# STSPIN32F0A-bldc-driver.net
KiCad netlist of a schematic drawn in Altium Designer
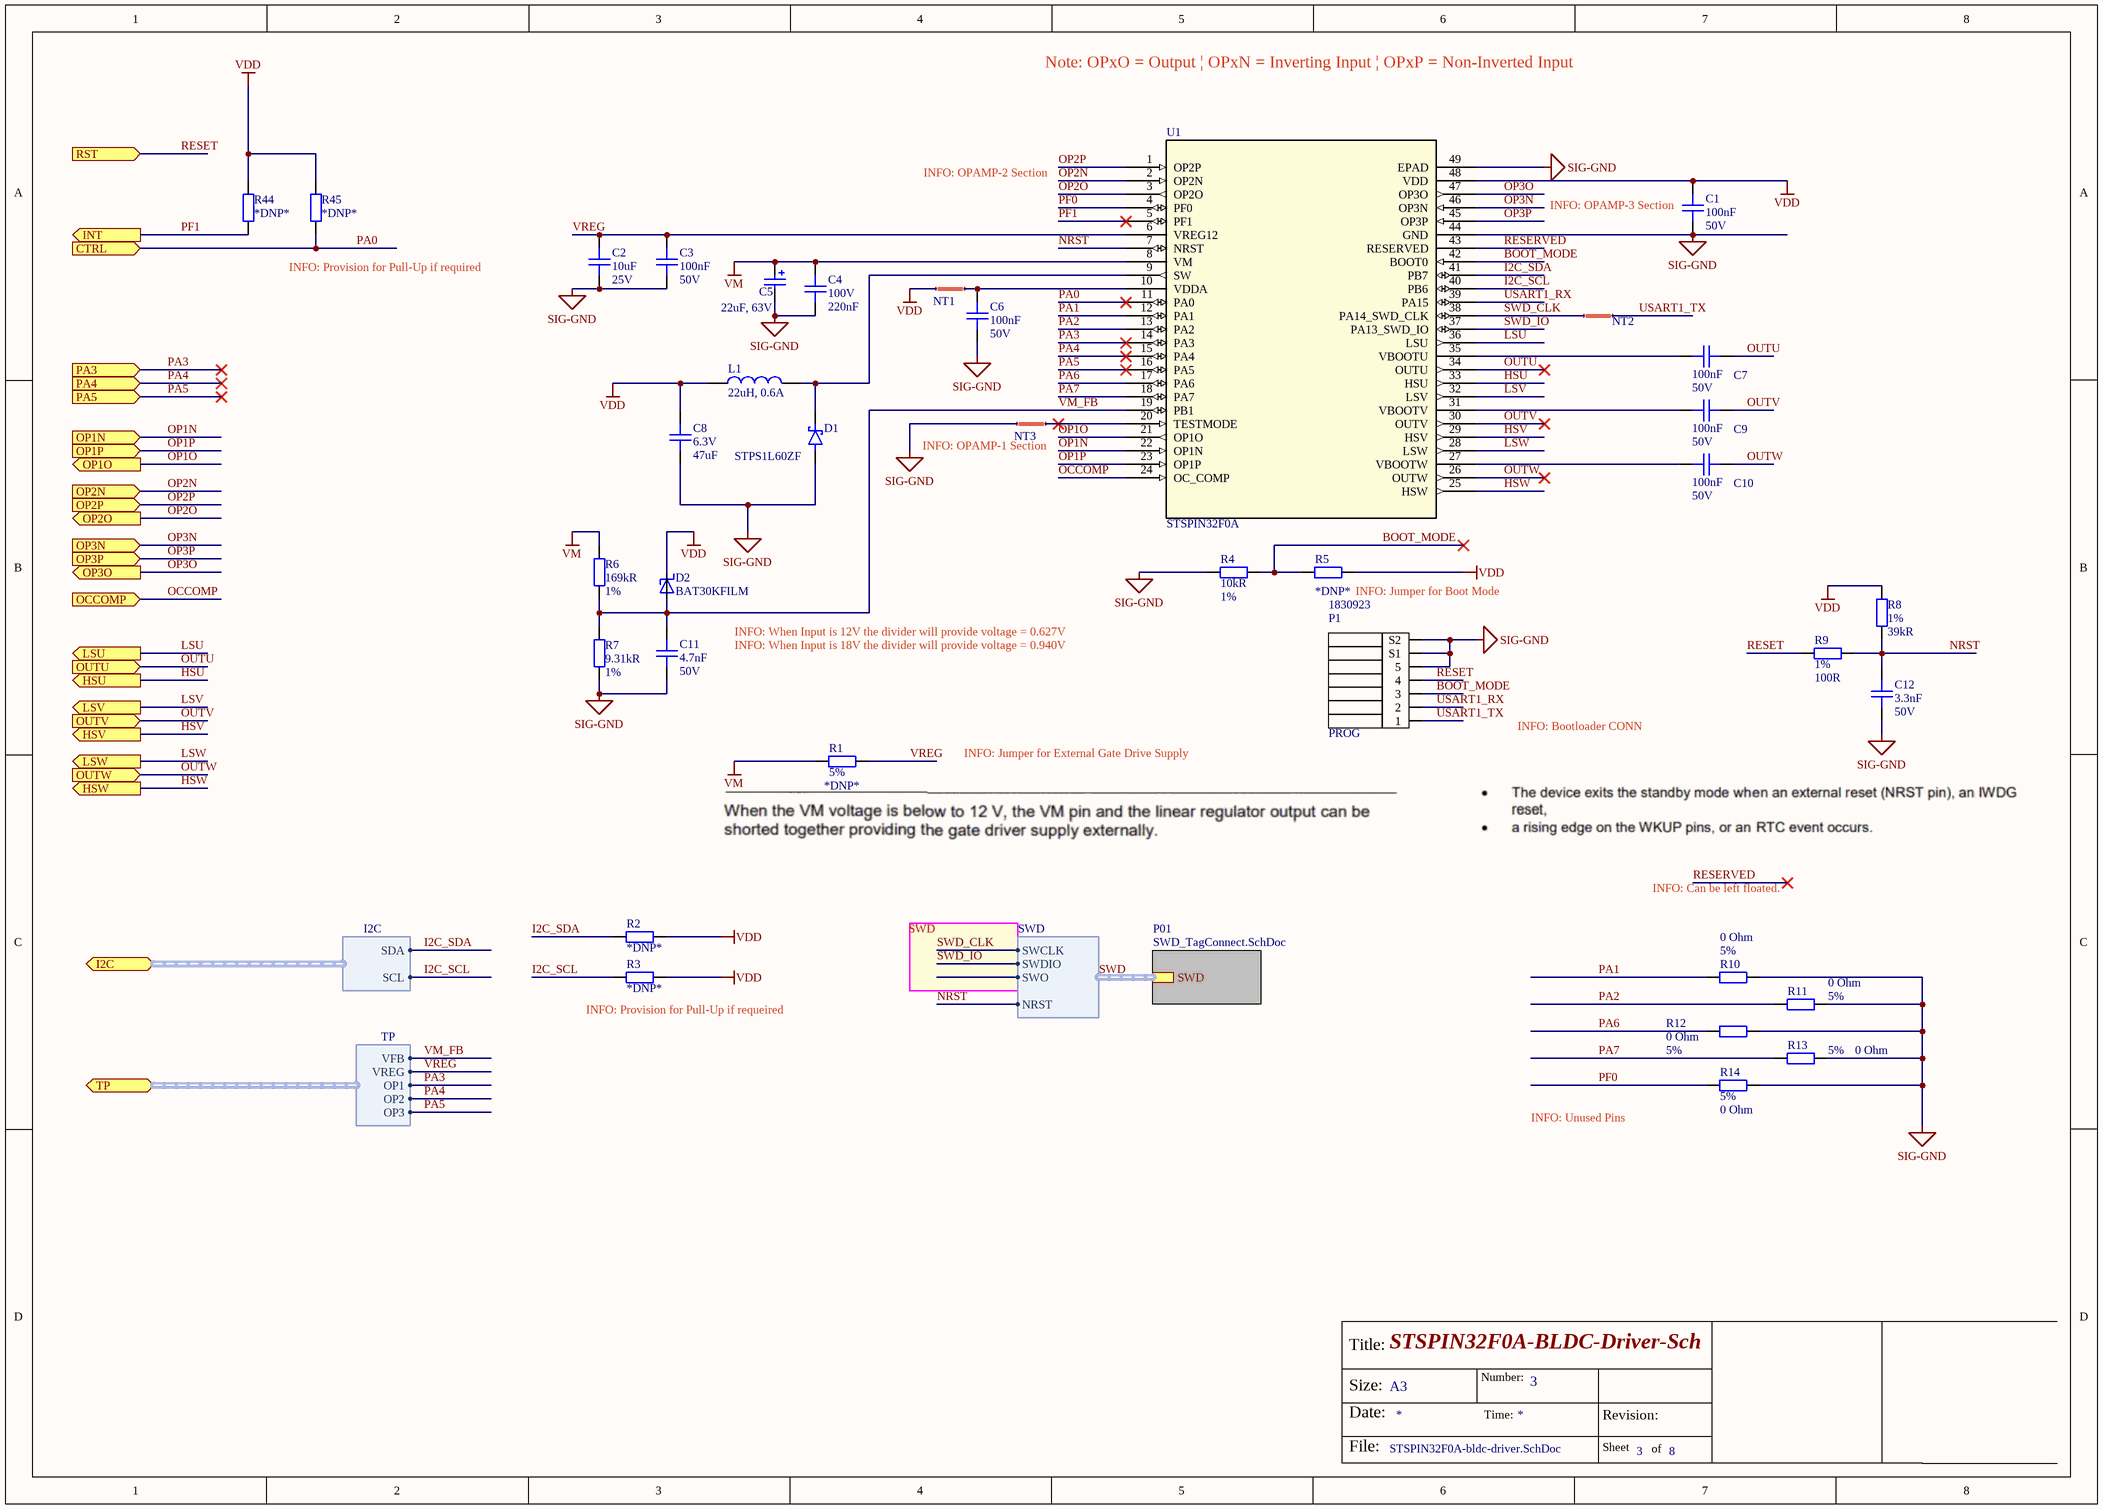
[diagram p0: STSPIN32F0A-bldc-driver.SchDoc]

(export (version "E")
  (design (tool "Eeschema 10.0.6"))
  (components
    (comp (ref "C1")
      (value "CAP CER 0.1UF 50V X7R 0402")
      (footprint "C0402")
      (description "0.1µF ±10% 50V Ceramic Capacitor X7R 0402 (1005 Metric)")
      (fields
        (field (name "MANUFACTURER") "TDK")
        (field (name "MANUFACTURER PART NUMBER") "CGA2B3X7R1H104K050BB")
        (field (name "CAPACITANCE") "100nF")
        (field (name "VOLTAGE") "50V")
      )
      (libsource (lib "Control_Board_Model_C201") (part "CAP CER 0.1UF 50V X7R 0402"))
    )
    (comp (ref "C2")
      (value "CAP CER 10UF 25V X7R 1206")
      (footprint "C1206")
      (description "10µF ±10% 25V Ceramic Capacitor X7R 1206 (3216 Metric)")
      (fields
        (field (name "MANUFACTURER") "Yageo")
        (field (name "MANUFACTURER PART NUMBER") "CC1206KKX7R8BB106")
        (field (name "CAPACITANCE") "10uF")
        (field (name "VOLTAGE RATING") "25V")
      )
      (libsource (lib "Control_Board_Model_C201") (part "CAP CER 10UF 25V X7R 1206"))
    )
    (comp (ref "C3")
      (value "CAP CER 0.1UF 50V X7R 0402")
      (footprint "C0402")
      (description "0.1µF ±10% 50V Ceramic Capacitor X7R 0402 (1005 Metric)")
      (fields
        (field (name "MANUFACTURER") "TDK")
        (field (name "MANUFACTURER PART NUMBER") "CGA2B3X7R1H104K050BB")
        (field (name "CAPACITANCE") "100nF")
        (field (name "VOLTAGE") "50V")
      )
      (libsource (lib "Control_Board_Model_C201") (part "CAP CER 0.1UF 50V X7R 0402"))
    )
    (comp (ref "C4")
      (value "CAP CER 220nF 100V X7R 0805")
      (footprint "C0805")
      (description "220nF ±10% 100V Ceramic Capacitor X7R 0805 (2012 Metric)")
      (fields
        (field (name "MANUFACTURER") "KEMET")
        (field (name "MANUFACTURER PART NUMBER") "C0805C224K1RECAUTO")
        (field (name "VOLTAGE RATING") "100V")
        (field (name "CAPACITANCE") "220nF")
      )
      (libsource (lib "Control_Board_Model_C201") (part "CAP CER 22UF 10V X5R 0805"))
    )
    (comp (ref "C5")
      (value "22uF, 63V")
      (footprint "WCAP-ASLL_D6.3H7.7")
      (description "WCAP-ASLL Aluminum Electrolytic Capacitor, V-Chip, SMT, D6.3xH7.7mm, 22uF, 63V")
      (fields
        (field (name "MANUFACTURER PART NUMBER") "865060745003")
        (field (name "MANUFACTURER") "Wurth Elektronik")
      )
      (libsource (lib "Altium_WCAP-ASLL (rev20b)") (part "865060745003"))
    )
    (comp (ref "C6")
      (value "CAP CER 0.1UF 50V X7R 0402")
      (footprint "C0402")
      (description "0.1µF ±10% 50V Ceramic Capacitor X7R 0402 (1005 Metric)")
      (fields
        (field (name "MANUFACTURER") "TDK")
        (field (name "MANUFACTURER PART NUMBER") "CGA2B3X7R1H104K050BB")
        (field (name "CAPACITANCE") "100nF")
        (field (name "VOLTAGE") "50V")
      )
      (libsource (lib "Control_Board_Model_C201") (part "CAP CER 0.1UF 50V X7R 0402"))
    )
    (comp (ref "C7")
      (value "CAP CER 0.1UF 50V X7R 0402")
      (footprint "C0402")
      (description "0.1µF ±10% 50V Ceramic Capacitor X7R 0402 (1005 Metric)")
      (fields
        (field (name "MANUFACTURER") "TDK")
        (field (name "MANUFACTURER PART NUMBER") "CGA2B3X7R1H104K050BB")
        (field (name "CAPACITANCE") "100nF")
        (field (name "VOLTAGE") "50V")
      )
      (libsource (lib "Control_Board_Model_C201") (part "CAP CER 0.1UF 50V X7R 0402"))
    )
    (comp (ref "C8")
      (value "CAP CER 47UF 6.3V X5R 0603")
      (footprint "C0603")
      (description "47µF ±20% 6.3V Ceramic Capacitor X5R 0603 (1608 Metric)")
      (fields
        (field (name "MANUFACTURER") "AVX Corporation")
        (field (name "MANUFACTURER PART NUMBER") "06036D476MAT2A")
        (field (name "VOLTAGE RATING") "6.3V")
        (field (name "CAPACITANCE") "47uF")
      )
      (libsource (lib "Control_Board_Model_C201") (part "CAP CER 4.7UF 16V X5R 0603"))
    )
    (comp (ref "C9")
      (value "CAP CER 0.1UF 50V X7R 0402")
      (footprint "C0402")
      (description "0.1µF ±10% 50V Ceramic Capacitor X7R 0402 (1005 Metric)")
      (fields
        (field (name "MANUFACTURER") "TDK")
        (field (name "MANUFACTURER PART NUMBER") "CGA2B3X7R1H104K050BB")
        (field (name "CAPACITANCE") "100nF")
        (field (name "VOLTAGE") "50V")
      )
      (libsource (lib "Control_Board_Model_C201") (part "CAP CER 0.1UF 50V X7R 0402"))
    )
    (comp (ref "C10")
      (value "CAP CER 0.1UF 50V X7R 0402")
      (footprint "C0402")
      (description "0.1µF ±10% 50V Ceramic Capacitor X7R 0402 (1005 Metric)")
      (fields
        (field (name "MANUFACTURER") "TDK")
        (field (name "MANUFACTURER PART NUMBER") "CGA2B3X7R1H104K050BB")
        (field (name "CAPACITANCE") "100nF")
        (field (name "VOLTAGE") "50V")
      )
      (libsource (lib "Control_Board_Model_C201") (part "CAP CER 0.1UF 50V X7R 0402"))
    )
    (comp (ref "C11")
      (value "CAP CER 4.7nF 50V X7R 0402")
      (footprint "C0402")
      (description "4.7nF ±10% 50V Ceramic Capacitor X7R 0402 (1005 Metric)")
      (fields
        (field (name "MANUFACTURER") "KEMET")
        (field (name "MANUFACTURER PART NUMBER") "C0402C472K5RECAUTO")
        (field (name "CAPACITANCE") "4.7nF")
        (field (name "VOLTAGE RATING") "50V")
      )
      (libsource (lib "Control_Board_Model_C201") (part "CAP CER 0.047UF 50V X7R 0402"))
    )
    (comp (ref "C12")
      (value "CAP CER 0.1UF 50V X7R 0402")
      (footprint "C0402")
      (description "0.1µF ±10% 50V Ceramic Capacitor X7R 0402 (1005 Metric)")
      (fields
        (field (name "MANUFACTURER") "KEMET")
        (field (name "MANUFACTURER PART NUMBER") "C0402C332K5RECAUTO")
        (field (name "CAPACITANCE") "3.3nF")
        (field (name "VOLTAGE") "50V")
      )
      (libsource (lib "Control_Board_Model_C201") (part "CAP CER 0.1UF 50V X7R 0402"))
    )
    (comp (ref "D1")
      (value "STPS1L60ZF")
      (footprint "DIO_STPS1L60ZF")
      (description "Diode Schottky 60V 1A Surface Mount SOD-123F")
      (fields
        (field (name "MANUFACTURER") "STMicroelectronics")
        (field (name "MANUFACTURER PART NUMBER") "STPS1L60ZF")
      )
      (libsource (lib "STPS1L60ZF") (part "STPS1L60ZF"))
    )
    (comp (ref "D2")
      (value "BAT30KFILM")
      (footprint "SOD523")
      (description "Schottky Diode 30V 300mA (DC) Surface Mount SOD-523")
      (fields (field (name "MANUFACTURER") "STMicroelectronics"))
      (libsource (lib "BAT30KFILM") (part "BAT30KFILM"))
    )
    (comp (ref "L1")
      (value "22uH, 0.6A")
      (footprint "WE-LQS_3015")
      (description "WE-LQS SMT Power Inductor, size 3015, 22uH, 0.6A")
      (fields
        (field (name "MANUFACTURER") "Wurth Elektronik")
        (field (name "MANUFACTURER PART NUMBER") "74404032220")
      )
      (libsource (lib "WE-LQS (rev20b)") (part "74404032220"))
    )
    (comp (ref "NT1")
      (value "Net Tie")
      (footprint "Net Tie 6x30mil")
      (libsource (lib "Control_Board_Model_C201") (part "Net Tie Line"))
    )
    (comp (ref "NT2")
      (value "Net Tie")
      (footprint "Net Tie 6x30mil")
      (libsource (lib "Control_Board_Model_C201") (part "Net Tie Line"))
    )
    (comp (ref "NT3")
      (value "Net Tie")
      (footprint "Net Tie 6x30mil")
      (libsource (lib "Control_Board_Model_C201") (part "Net Tie Line"))
    )
    (comp (ref "P1")
      (value "PROG")
      (footprint "JST_S5B-ZR-SM4A-TF(LF)(SN)")
      (description "Connector Header SMD, Right Angle 4 position 0.059\" (1.50mm)")
      (fields
        (field (name "MANUFACTURER") "JST")
        (field (name "MANUFACTURER PART NUMBER") "S4B-ZR-SM4A-TF")
        (field (name "SUPPLIER PART NUMBER 1") "1830923")
      )
      (libsource (lib "JST-ZR-v1.3") (part "JST_S5B-ZR-SM4A-TF(LF)(SN)"))
    )
    (comp (ref "R1")
      (value "*DNP*")
      (footprint "R0402")
      (description "0 Ohms Jumper 0.063W, 1/16W Chip Resistor 0402 (1005 Metric) Moisture Resistant Thick Film")
      (fields
        (field (name "MANUFACTURER") "Yageo")
        (field (name "MANUFACTURER PART NUMBER") "RC0402JR-070RL")
        (field (name "TOLERANCE") "5%")
      )
      (libsource (lib "Control_Board_Model_C201") (part "RES SMD 0 OHM JUMPER 1/16W 0402"))
    )
    (comp (ref "R2")
      (value "RES SMD 4.75K OHM 1% 1/16W 0402")
      (footprint "R0402")
      (description "4.75 kOhms ±1% 0.063W, 1/16W Chip Resistor 0402 (1005 Metric) Moisture Resistant Thick Film")
      (fields
        (field (name "MANUFACTURER") "Yageo")
        (field (name "MANUFACTURER PART NUMBER") "RC0402FR-074K75P")
        (field (name "RESISTANCE") "*DNP*")
      )
      (libsource (lib "Control_Board_Model_C201") (part "RES SMD 4.75K OHM 1% 1/16W 0402"))
    )
    (comp (ref "R3")
      (value "RES SMD 4.75K OHM 1% 1/16W 0402")
      (footprint "R0402")
      (description "4.75 kOhms ±1% 0.063W, 1/16W Chip Resistor 0402 (1005 Metric) Moisture Resistant Thick Film")
      (fields
        (field (name "MANUFACTURER") "Yageo")
        (field (name "MANUFACTURER PART NUMBER") "RC0402FR-074K75P")
        (field (name "RESISTANCE") "*DNP*")
      )
      (libsource (lib "Control_Board_Model_C201") (part "RES SMD 4.75K OHM 1% 1/16W 0402"))
    )
    (comp (ref "R4")
      (value "RES SMD 10K OHM 1% 1/16W 0402")
      (footprint "R0402")
      (description "10 kOhms ±1% 0.063W, 1/16W Chip Resistor 0402 (1005 Metric) Moisture Resistant Thick Film")
      (fields
        (field (name "MANUFACTURER") "Yageo")
        (field (name "MANUFACTURER PART NUMBER") "RC0402FR-0710KP")
        (field (name "RESISTANCE") "10kR")
        (field (name "TOLERANCE") "1%")
      )
      (libsource (lib "Control_Board_Model_C201") (part "RES SMD 10K OHM 1% 1/16W 0402"))
    )
    (comp (ref "R5")
      (value "*DNP*")
      (footprint "R0402")
      (description "0 Ohms Jumper 0.063W, 1/16W Chip Resistor 0402 (1005 Metric) Moisture Resistant Thick Film")
      (fields
        (field (name "MANUFACTURER") "Yageo")
        (field (name "MANUFACTURER PART NUMBER") "RC0402JR-070RL")
      )
      (libsource (lib "Control_Board_Model_C201") (part "RES SMD 0 OHM JUMPER 1/16W 0402"))
    )
    (comp (ref "R6")
      (value "RES SMD 169 KOHM 1% 1/8W 0603")
      (footprint "R0603")
      (description "169 kOhms ±1% 0.125W, 1/8W Chip Resistor 0603 (1608 Metric) Automotive AEC-Q200 Thick Film")
      (fields
        (field (name "MANUFACTURER PART NUMBER") "TNPW0603169KBEEA")
        (field (name "MANUFACTURER") "Vishay Dale")
        (field (name "RESISTANCE") "169kR")
        (field (name "TOLERANCE") "1%")
      )
      (libsource (lib "Control_Board_Model_C201") (part "RES SMD 2.26 OHM 1% 1/10W 0603"))
    )
    (comp (ref "R7")
      (value "RES SMD 9.31 KOHM 1% 1/8W 0603")
      (footprint "R0603")
      (description "9.31 kOhms ±1% 0.125W, 1/8W Chip Resistor 0603 (1608 Metric) Automotive AEC-Q200 Thick Film")
      (fields
        (field (name "MANUFACTURER PART NUMBER") "TNPW06039K31BEEA")
        (field (name "MANUFACTURER") "Vishay Dale")
        (field (name "RESISTANCE") "9.31kR")
        (field (name "TOLERANCE") "1%")
      )
      (libsource (lib "Control_Board_Model_C201") (part "RES SMD 2.26 OHM 1% 1/10W 0603"))
    )
    (comp (ref "R8")
      (value "RES SMD 39K OHM 1% 1/10W 0402")
      (footprint "R0402")
      (description "39 kOhms ±1% 0.100W, 1/10W Chip Resistor 0402 (1005 Metric) Moisture Resistant Thick Film")
      (fields
        (field (name "MANUFACTURER") "Panasonic Electronic Components")
        (field (name "MANUFACTURER PART NUMBER") "ERJ-2RKF3902X")
        (field (name "TOLERANCE") "1%")
        (field (name "RESISTANCE") "39kR")
      )
      (libsource (lib "Control_Board_Model_C201") (part "RES SMD 54.9K OHM 1% 1/16W 0402"))
    )
    (comp (ref "R9")
      (value "RES SMD 100 OHM 1% 1/16W 0402")
      (footprint "R0402")
      (description "100 Ohms ±1% 0.063W, 1/16W Chip Resistor 0402 (1005 Metric) Moisture Resistant Thick Film")
      (fields
        (field (name "MANUFACTURER") "Yageo")
        (field (name "MANUFACTURER PART NUMBER") "RC0402FR-07100RL")
        (field (name "TOLERANCE") "1%")
        (field (name "RESISTANCE") "100R")
      )
      (libsource (lib "Control_Board_Model_C201") (part "RES SMD 100 OHM 1% 1/16W 0402"))
    )
    (comp (ref "R10")
      (value "RES SMD 0 OHM JUMPER 1/16W 0402")
      (footprint "R0402")
      (description "0 Ohms Jumper 0.063W, 1/16W Chip Resistor 0402 (1005 Metric) Moisture Resistant Thick Film")
      (fields
        (field (name "MANUFACTURER") "Yageo")
        (field (name "MANUFACTURER PART NUMBER") "RC0402JR-070RL")
        (field (name "TOLERANCE") "5%")
        (field (name "RESISTANCE") "0 Ohm")
      )
      (libsource (lib "Control_Board_Model_C201") (part "RES SMD 0 OHM JUMPER 1/16W 0402"))
    )
    (comp (ref "R11")
      (value "RES SMD 0 OHM JUMPER 1/16W 0402")
      (footprint "R0402")
      (description "0 Ohms Jumper 0.063W, 1/16W Chip Resistor 0402 (1005 Metric) Moisture Resistant Thick Film")
      (fields
        (field (name "MANUFACTURER") "Yageo")
        (field (name "MANUFACTURER PART NUMBER") "RC0402JR-070RL")
        (field (name "TOLERANCE") "5%")
        (field (name "RESISTANCE") "0 Ohm")
      )
      (libsource (lib "Control_Board_Model_C201") (part "RES SMD 0 OHM JUMPER 1/16W 0402"))
    )
    (comp (ref "R12")
      (value "RES SMD 0 OHM JUMPER 1/16W 0402")
      (footprint "R0402")
      (description "0 Ohms Jumper 0.063W, 1/16W Chip Resistor 0402 (1005 Metric) Moisture Resistant Thick Film")
      (fields
        (field (name "MANUFACTURER") "Yageo")
        (field (name "MANUFACTURER PART NUMBER") "RC0402JR-070RL")
        (field (name "TOLERANCE") "5%")
        (field (name "RESISTANCE") "0 Ohm")
      )
      (libsource (lib "Control_Board_Model_C201") (part "RES SMD 0 OHM JUMPER 1/16W 0402"))
    )
    (comp (ref "R13")
      (value "RES SMD 0 OHM JUMPER 1/16W 0402")
      (footprint "R0402")
      (description "0 Ohms Jumper 0.063W, 1/16W Chip Resistor 0402 (1005 Metric) Moisture Resistant Thick Film")
      (fields
        (field (name "MANUFACTURER") "Yageo")
        (field (name "MANUFACTURER PART NUMBER") "RC0402JR-070RL")
        (field (name "TOLERANCE") "5%")
        (field (name "RESISTANCE") "0 Ohm")
      )
      (libsource (lib "Control_Board_Model_C201") (part "RES SMD 0 OHM JUMPER 1/16W 0402"))
    )
    (comp (ref "R14")
      (value "RES SMD 0 OHM JUMPER 1/16W 0402")
      (footprint "R0402")
      (description "0 Ohms Jumper 0.063W, 1/16W Chip Resistor 0402 (1005 Metric) Moisture Resistant Thick Film")
      (fields
        (field (name "MANUFACTURER") "Yageo")
        (field (name "MANUFACTURER PART NUMBER") "RC0402JR-070RL")
        (field (name "TOLERANCE") "5%")
        (field (name "RESISTANCE") "0 Ohm")
      )
      (libsource (lib "Control_Board_Model_C201") (part "RES SMD 0 OHM JUMPER 1/16W 0402"))
    )
    (comp (ref "R44")
      (value "*DNP*")
      (footprint "R0402")
      (description "0 Ohms Jumper 0.063W, 1/16W Chip Resistor 0402 (1005 Metric) Moisture Resistant Thick Film")
      (fields
        (field (name "MANUFACTURER") "Yageo")
        (field (name "MANUFACTURER PART NUMBER") "RC0402JR-070RL")
      )
      (libsource (lib "") (part "RES SMD 0 OHM JUMPER 1/16W 0402_1"))
    )
    (comp (ref "R45")
      (value "*DNP*")
      (footprint "R0402")
      (description "0 Ohms Jumper 0.063W, 1/16W Chip Resistor 0402 (1005 Metric) Moisture Resistant Thick Film")
      (fields
        (field (name "MANUFACTURER") "Yageo")
        (field (name "MANUFACTURER PART NUMBER") "RC0402JR-070RL")
      )
      (libsource (lib "") (part "RES SMD 0 OHM JUMPER 1/16W 0402_1"))
    )
    (comp (ref "U1")
      (value "STSPIN32F0A")
      (footprint "VFQFPN-48_7x7x1mm_STM")
      (description "No Description Available")
      (fields
        (field (name "MANUFACTURER") "STMicroelectronics")
        (field (name "COPYRIGHT") "Copyright (C) 2018 Accelerated Designs. All rights reserved")
      )
      (libsource (lib "STSPIN32F0A") (part "STSPIN32F0A"))
    )
  )
  (nets
    (net (code "4") (name "/BOOT_MODE") (class "Default")
      (node (ref "P1") (pin "3") (pinfunction "3_3") (pintype "passive"))
      (node (ref "R4") (pin "1") (pinfunction "1_1") (pintype "passive"))
      (node (ref "R5") (pin "1") (pinfunction "1_1") (pintype "passive"))
      (node (ref "U1") (pin "42") (pinfunction "BOOT0_42") (pintype "input"))
    )
    (net (code "5") (name "/HSU") (class "Default")
      (node (ref "U1") (pin "33") (pinfunction "HSU_33") (pintype "output"))
    )
    (net (code "6") (name "/HSV") (class "Default")
      (node (ref "U1") (pin "29") (pinfunction "HSV_29") (pintype "output"))
    )
    (net (code "7") (name "/HSW") (class "Default")
      (node (ref "U1") (pin "25") (pinfunction "HSW_25") (pintype "output"))
    )
    (net (code "8") (name "/I2C_SCL") (class "Default")
      (node (ref "R3") (pin "1") (pinfunction "1_1") (pintype "passive"))
      (node (ref "U1") (pin "40") (pinfunction "PB6_40") (pintype "bidirectional"))
    )
    (net (code "9") (name "/I2C_SDA") (class "Default")
      (node (ref "R2") (pin "1") (pinfunction "1_1") (pintype "passive"))
      (node (ref "U1") (pin "41") (pinfunction "PB7_41") (pintype "bidirectional"))
    )
    (net (code "10") (name "/LSU") (class "Default")
      (node (ref "U1") (pin "36") (pinfunction "LSU_36") (pintype "output"))
    )
    (net (code "11") (name "/LSV") (class "Default")
      (node (ref "U1") (pin "32") (pinfunction "LSV_32") (pintype "output"))
    )
    (net (code "12") (name "/LSW") (class "Default")
      (node (ref "U1") (pin "28") (pinfunction "LSW_28") (pintype "output"))
    )
    (net (code "13") (name "/NRST") (class "Default")
      (node (ref "C12") (pin "2") (pinfunction "2_2") (pintype "passive"))
      (node (ref "R8") (pin "1") (pinfunction "1_1") (pintype "passive"))
      (node (ref "R9") (pin "1") (pinfunction "1_1") (pintype "passive"))
      (node (ref "U1") (pin "7") (pinfunction "NRST_7") (pintype "bidirectional"))
    )
    (net (code "14") (name "/OCCOMP") (class "Default")
      (node (ref "U1") (pin "24") (pinfunction "OC_COMP_24") (pintype "input"))
    )
    (net (code "15") (name "/OP1N") (class "Default")
      (node (ref "U1") (pin "22") (pinfunction "OP1N_22") (pintype "input"))
    )
    (net (code "16") (name "/OP1O") (class "Default")
      (node (ref "U1") (pin "21") (pinfunction "OP1O_21") (pintype "output"))
    )
    (net (code "17") (name "/OP1P") (class "Default")
      (node (ref "U1") (pin "23") (pinfunction "OP1P_23") (pintype "input"))
    )
    (net (code "18") (name "/OP2N") (class "Default")
      (node (ref "U1") (pin "2") (pinfunction "OP2N_2") (pintype "input"))
    )
    (net (code "19") (name "/OP2O") (class "Default")
      (node (ref "U1") (pin "3") (pinfunction "OP2O_3") (pintype "output"))
    )
    (net (code "20") (name "/OP2P") (class "Default")
      (node (ref "U1") (pin "1") (pinfunction "OP2P_1") (pintype "input"))
    )
    (net (code "21") (name "/OP3N") (class "Default")
      (node (ref "U1") (pin "46") (pinfunction "OP3N_46") (pintype "input"))
    )
    (net (code "22") (name "/OP3O") (class "Default")
      (node (ref "U1") (pin "47") (pinfunction "OP3O_47") (pintype "output"))
    )
    (net (code "23") (name "/OP3P") (class "Default")
      (node (ref "U1") (pin "45") (pinfunction "OP3P_45") (pintype "input"))
    )
    (net (code "24") (name "/OUTU") (class "Default")
      (node (ref "C7") (pin "2") (pinfunction "2_2") (pintype "passive"))
      (node (ref "U1") (pin "34") (pinfunction "OUTU_34") (pintype "output"))
    )
    (net (code "25") (name "/OUTV") (class "Default")
      (node (ref "C9") (pin "1") (pinfunction "1_1") (pintype "passive"))
      (node (ref "U1") (pin "30") (pinfunction "OUTV_30") (pintype "output"))
    )
    (net (code "26") (name "/OUTW") (class "Default")
      (node (ref "C10") (pin "1") (pinfunction "1_1") (pintype "passive"))
      (node (ref "U1") (pin "26") (pinfunction "OUTW_26") (pintype "output"))
    )
    (net (code "27") (name "/PA0") (class "Default")
      (node (ref "R45") (pin "1") (pinfunction "1_1") (pintype "passive"))
      (node (ref "U1") (pin "11") (pinfunction "PA0_11") (pintype "bidirectional"))
    )
    (net (code "28") (name "/PA1") (class "Default")
      (node (ref "R10") (pin "1") (pinfunction "1_1") (pintype "passive"))
      (node (ref "U1") (pin "12") (pinfunction "PA1_12") (pintype "bidirectional"))
    )
    (net (code "29") (name "/PA2") (class "Default")
      (node (ref "R11") (pin "1") (pinfunction "1_1") (pintype "passive"))
      (node (ref "U1") (pin "13") (pinfunction "PA2_13") (pintype "bidirectional"))
    )
    (net (code "30") (name "/PA3") (class "Default")
      (node (ref "U1") (pin "14") (pinfunction "PA3_14") (pintype "bidirectional+no_connect"))
    )
    (net (code "31") (name "/PA4") (class "Default")
      (node (ref "U1") (pin "15") (pinfunction "PA4_15") (pintype "bidirectional+no_connect"))
    )
    (net (code "32") (name "/PA5") (class "Default")
      (node (ref "U1") (pin "16") (pinfunction "PA5_16") (pintype "bidirectional+no_connect"))
    )
    (net (code "33") (name "/PA6") (class "Default")
      (node (ref "R12") (pin "1") (pinfunction "1_1") (pintype "passive"))
      (node (ref "U1") (pin "17") (pinfunction "PA6_17") (pintype "bidirectional"))
    )
    (net (code "34") (name "/PA7") (class "Default")
      (node (ref "R13") (pin "1") (pinfunction "1_1") (pintype "passive"))
      (node (ref "U1") (pin "18") (pinfunction "PA7_18") (pintype "bidirectional"))
    )
    (net (code "35") (name "/PF0") (class "Default")
      (node (ref "R14") (pin "1") (pinfunction "1_1") (pintype "passive"))
      (node (ref "U1") (pin "4") (pinfunction "PF0_4") (pintype "bidirectional"))
    )
    (net (code "36") (name "/PF1") (class "Default")
      (node (ref "R44") (pin "1") (pinfunction "1_1") (pintype "passive"))
      (node (ref "U1") (pin "5") (pinfunction "PF1_5") (pintype "bidirectional"))
    )
    (net (code "37") (name "/RESERVED") (class "Default")
      (node (ref "U1") (pin "43") (pinfunction "RESERVED_43") (pintype "passive"))
    )
    (net (code "38") (name "/RESET") (class "Default")
      (node (ref "P1") (pin "4") (pinfunction "4_4") (pintype "passive"))
      (node (ref "R9") (pin "2") (pinfunction "2_2") (pintype "passive"))
    )
    (net (code "39") (name "/SWD_CLK") (class "Default")
      (node (ref "NT2") (pin "1") (pintype "passive"))
      (node (ref "U1") (pin "38") (pinfunction "PA14_SWD_CLK_38") (pintype "bidirectional"))
    )
    (net (code "40") (name "/SWD_IO") (class "Default")
      (node (ref "U1") (pin "37") (pinfunction "PA13_SWD_IO_37") (pintype "bidirectional"))
    )
    (net (code "42") (name "/USART1_RX") (class "Default")
      (node (ref "P1") (pin "2") (pinfunction "2_2") (pintype "passive"))
      (node (ref "U1") (pin "39") (pinfunction "PA15_39") (pintype "bidirectional"))
    )
    (net (code "43") (name "/USART1_TX") (class "Default")
      (node (ref "NT2") (pin "2") (pintype "passive"))
      (node (ref "P1") (pin "1") (pinfunction "1_1") (pintype "passive"))
    )
    (net (code "44") (name "/VM_FB") (class "Default")
      (node (ref "C11") (pin "2") (pinfunction "2_2") (pintype "passive"))
      (node (ref "D2") (pin "2") (pinfunction "A_2") (pintype "passive"))
      (node (ref "R6") (pin "1") (pinfunction "1_1") (pintype "passive"))
      (node (ref "R7") (pin "2") (pinfunction "2_2") (pintype "passive"))
      (node (ref "U1") (pin "19") (pinfunction "PB1_19") (pintype "bidirectional"))
    )
    (net (code "45") (name "/VREG") (class "Default")
      (node (ref "C2") (pin "2") (pinfunction "2_2") (pintype "passive"))
      (node (ref "C3") (pin "2") (pinfunction "2_2") (pintype "passive"))
      (node (ref "R1") (pin "2") (pinfunction "2_2") (pintype "passive"))
      (node (ref "U1") (pin "6") (pinfunction "VREG12_6") (pintype "power_in"))
    )
    (net (code "48") (name "Net-(D1-K)") (class "Default")
      (node (ref "D1") (pin "1") (pinfunction "K_1") (pintype "passive"))
      (node (ref "L1") (pin "2") (pinfunction "2_2") (pintype "passive"))
      (node (ref "U1") (pin "9") (pinfunction "SW_9") (pintype "output"))
    )
    (net (code "49") (name "Net-(U1-TESTMODE)") (class "Default")
      (node (ref "NT3") (pin "2") (pintype "passive"))
      (node (ref "U1") (pin "20") (pinfunction "TESTMODE_20") (pintype "input"))
    )
    (net (code "50") (name "Net-(U1-VBOOTU)") (class "Default")
      (node (ref "C7") (pin "1") (pinfunction "1_1") (pintype "passive"))
      (node (ref "U1") (pin "35") (pinfunction "VBOOTU_35") (pintype "power_in"))
    )
    (net (code "51") (name "Net-(U1-VBOOTV)") (class "Default")
      (node (ref "C9") (pin "2") (pinfunction "2_2") (pintype "passive"))
      (node (ref "U1") (pin "31") (pinfunction "VBOOTV_31") (pintype "power_in"))
    )
    (net (code "52") (name "Net-(U1-VBOOTW)") (class "Default")
      (node (ref "C10") (pin "2") (pinfunction "2_2") (pintype "passive"))
      (node (ref "U1") (pin "27") (pinfunction "VBOOTW_27") (pintype "power_in"))
    )
    (net (code "53") (name "Net-(U1-VDDA)") (class "Default")
      (node (ref "C6") (pin "2") (pinfunction "2_2") (pintype "passive"))
      (node (ref "NT1") (pin "2") (pintype "passive"))
      (node (ref "U1") (pin "10") (pinfunction "VDDA_10") (pintype "power_in"))
    )
    (net (code "54") (name "SIG-GND") (class "Default")
      (node (ref "C1") (pin "1") (pinfunction "1_1") (pintype "passive"))
      (node (ref "C11") (pin "1") (pinfunction "1_1") (pintype "passive"))
      (node (ref "C12") (pin "1") (pinfunction "1_1") (pintype "passive"))
      (node (ref "C2") (pin "1") (pinfunction "1_1") (pintype "passive"))
      (node (ref "C3") (pin "1") (pinfunction "1_1") (pintype "passive"))
      (node (ref "C4") (pin "1") (pinfunction "1_1") (pintype "passive"))
      (node (ref "C5") (pin "2") (pinfunction "N_2") (pintype "passive"))
      (node (ref "C6") (pin "1") (pinfunction "1_1") (pintype "passive"))
      (node (ref "C8") (pin "1") (pinfunction "1_1") (pintype "passive"))
      (node (ref "D1") (pin "2") (pinfunction "A_2") (pintype "passive"))
      (node (ref "NT3") (pin "1") (pintype "passive"))
      (node (ref "P1") (pin "5") (pinfunction "5_5") (pintype "passive"))
      (node (ref "P1") (pin "S1") (pinfunction "S1_S1") (pintype "passive"))
      (node (ref "P1") (pin "S2") (pinfunction "S2_S2") (pintype "passive"))
      (node (ref "R10") (pin "2") (pinfunction "2_2") (pintype "passive"))
      (node (ref "R11") (pin "2") (pinfunction "2_2") (pintype "passive"))
      (node (ref "R12") (pin "2") (pinfunction "2_2") (pintype "passive"))
      (node (ref "R13") (pin "2") (pinfunction "2_2") (pintype "passive"))
      (node (ref "R14") (pin "2") (pinfunction "2_2") (pintype "passive"))
      (node (ref "R4") (pin "2") (pinfunction "2_2") (pintype "passive"))
      (node (ref "R7") (pin "1") (pinfunction "1_1") (pintype "passive"))
      (node (ref "U1") (pin "44") (pinfunction "GND_44") (pintype "power_in"))
      (node (ref "U1") (pin "49") (pinfunction "EPAD_49") (pintype "passive"))
    )
    (net (code "55") (name "VDD") (class "Default")
      (node (ref "C1") (pin "2") (pinfunction "2_2") (pintype "passive"))
      (node (ref "C8") (pin "2") (pinfunction "2_2") (pintype "passive"))
      (node (ref "D2") (pin "1") (pinfunction "K_1") (pintype "passive"))
      (node (ref "L1") (pin "1") (pinfunction "1_1") (pintype "passive"))
      (node (ref "NT1") (pin "1") (pintype "passive"))
      (node (ref "R2") (pin "2") (pinfunction "2_2") (pintype "passive"))
      (node (ref "R3") (pin "2") (pinfunction "2_2") (pintype "passive"))
      (node (ref "R44") (pin "2") (pinfunction "2_2") (pintype "passive"))
      (node (ref "R45") (pin "2") (pinfunction "2_2") (pintype "passive"))
      (node (ref "R5") (pin "2") (pinfunction "2_2") (pintype "passive"))
      (node (ref "R8") (pin "2") (pinfunction "2_2") (pintype "passive"))
      (node (ref "U1") (pin "48") (pinfunction "VDD_48") (pintype "power_in"))
    )
    (net (code "56") (name "VM") (class "Default")
      (node (ref "C4") (pin "2") (pinfunction "2_2") (pintype "passive"))
      (node (ref "C5") (pin "1") (pinfunction "P_1") (pintype "passive"))
      (node (ref "R1") (pin "1") (pinfunction "1_1") (pintype "passive"))
      (node (ref "R6") (pin "2") (pinfunction "2_2") (pintype "passive"))
      (node (ref "U1") (pin "8") (pinfunction "VM_8") (pintype "power_in"))
    )
  )
)
